# Crazebird-v0_5.net
KiCad netlist of a schematic drawn in EAGLE
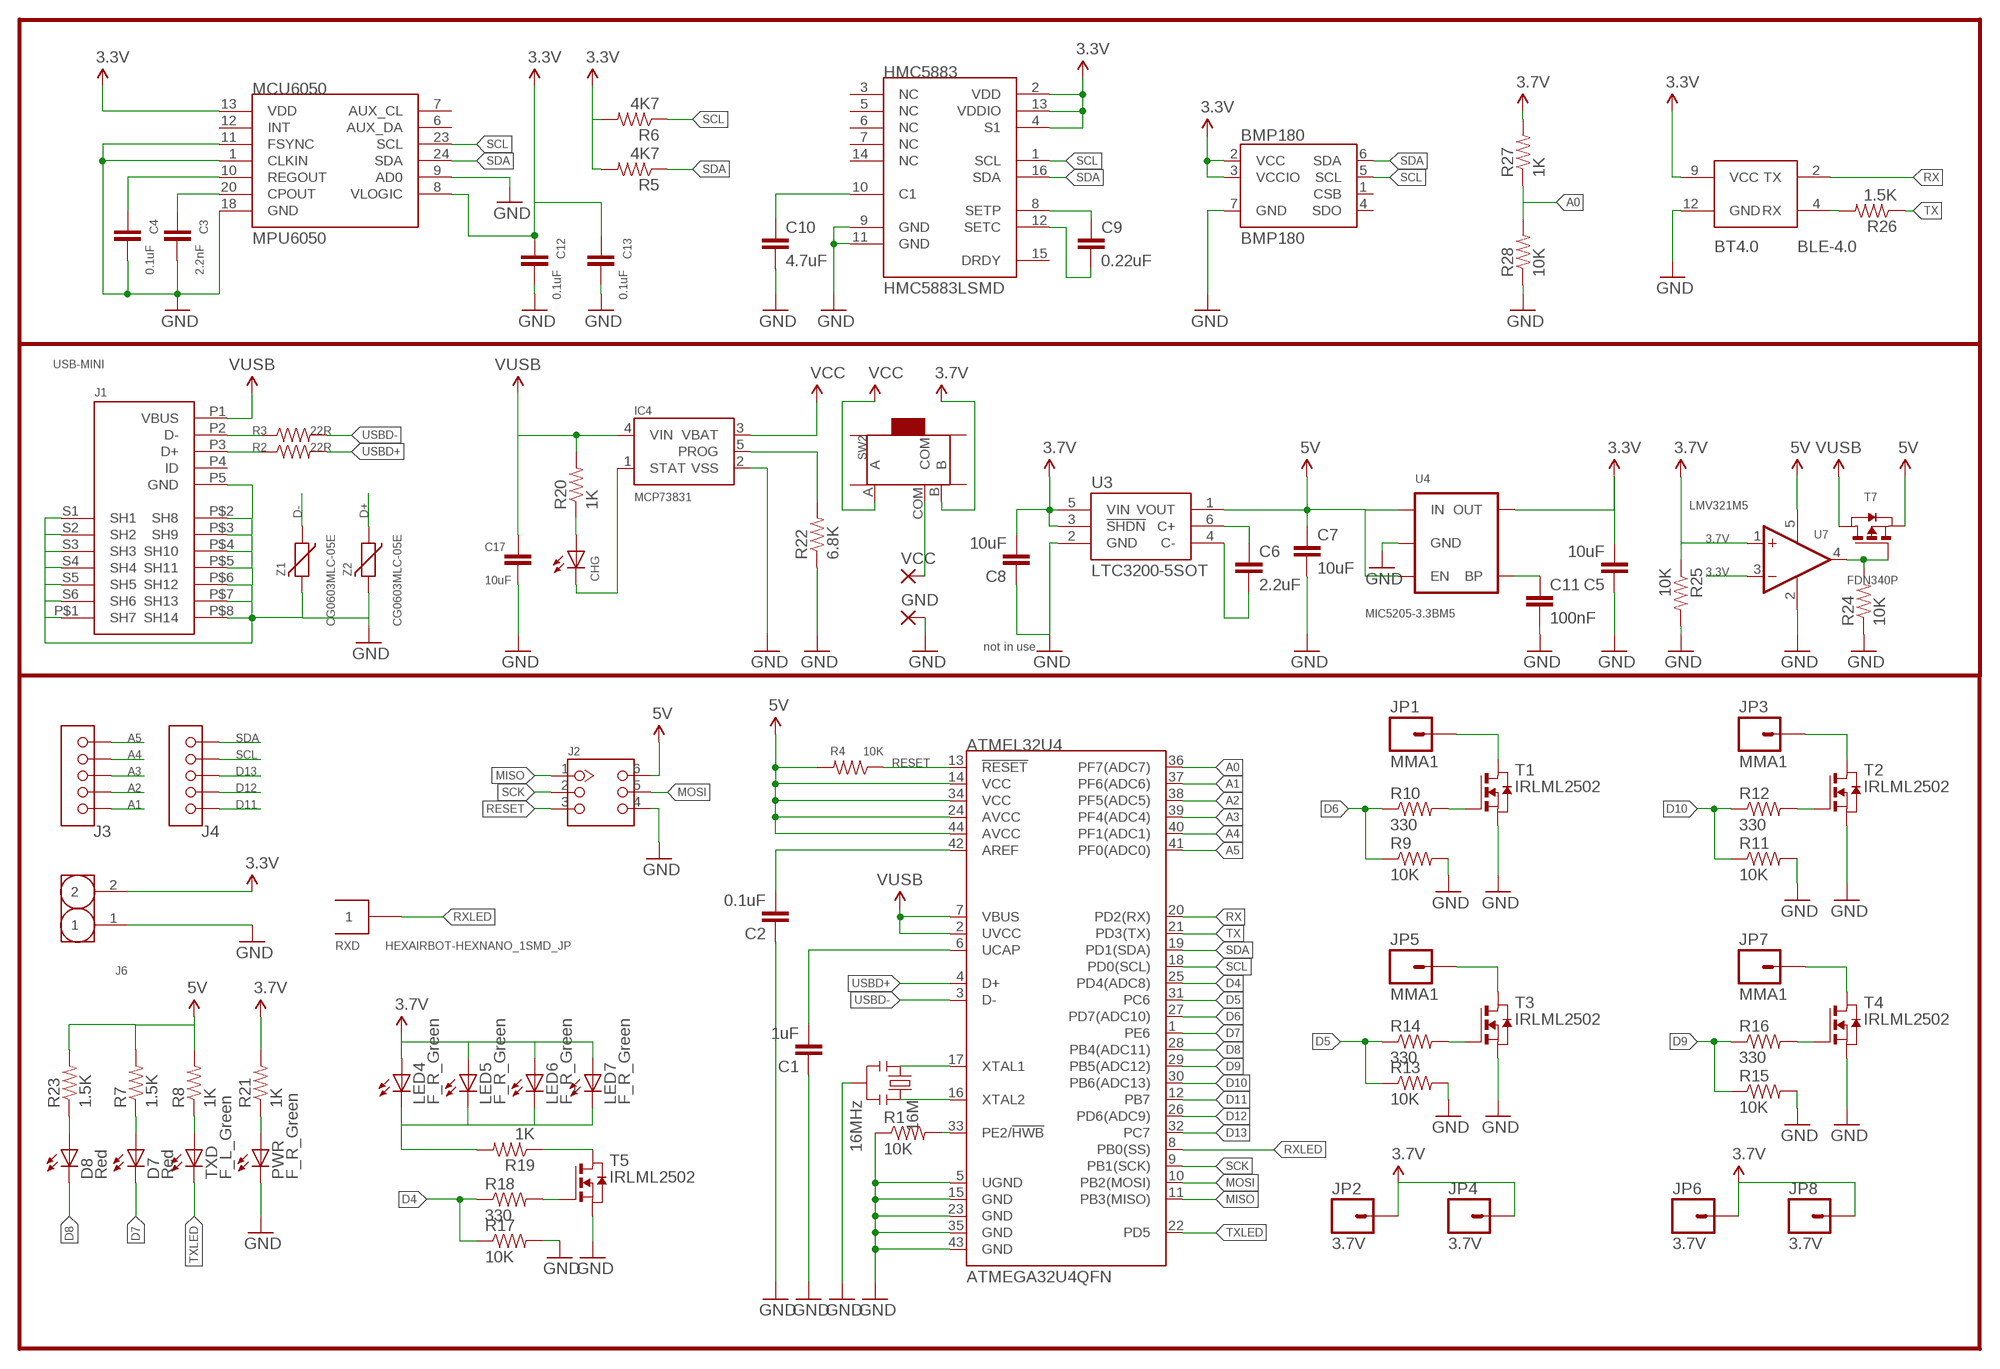
[diagram p0: schematic, sheet 1]

(export (version "E")
  (design (tool "Eeschema 10.0.6"))
  (components
    (comp (ref "16M")
      (value "16MHz")
      (footprint "eagle-import:RESONATOR-SMD")
      (libsource (lib "eagle-import") (part "RESONATOR16MHZ"))
    )
    (comp (ref "ATMEL32U4")
      (value "ATMEGA32U4QFN")
      (footprint "eagle-import:SPARKFUN-DIGITALIC_QFN-44")
      (libsource (lib "eagle-import") (part "ATMEGA32U4QFN"))
    )
    (comp (ref "BMP180")
      (value "BMP180")
      (footprint "eagle-import:BMP180")
      (libsource (lib "eagle-import") (part "BMP180"))
    )
    (comp (ref "BT4.0")
      (value "BLE-4.0")
      (footprint "eagle-import:HEXAIRBOT-HEXNANO_BLUETOOTH_HM11")
      (libsource (lib "eagle-import") (part "HEXAIRBOT-HEXNANO_BLUETOOTH_HM11"))
    )
    (comp (ref "C1")
      (value "1uF")
      (footprint "eagle-import:0402-CAP")
      (libsource (lib "eagle-import") (part "SparkFun-Passives_CAP0402-CAP"))
    )
    (comp (ref "C2")
      (value "0.1uF")
      (footprint "eagle-import:0402-CAP")
      (libsource (lib "eagle-import") (part "SparkFun-Passives_CAP0402-CAP"))
    )
    (comp (ref "C3")
      (value "2.2nF")
      (footprint "eagle-import:0402-CAP")
      (libsource (lib "eagle-import") (part "SparkFun-Passives_CAP0402-CAP"))
    )
    (comp (ref "C4")
      (value "0.1uF")
      (footprint "eagle-import:0402-CAP")
      (libsource (lib "eagle-import") (part "SparkFun-Passives_CAP0402-CAP"))
    )
    (comp (ref "C5")
      (value "10uF")
      (footprint "eagle-import:0402-CAP")
      (libsource (lib "eagle-import") (part "SparkFun-Passives_CAP0402-CAP"))
    )
    (comp (ref "C6")
      (value "2.2uF")
      (footprint "eagle-import:0603-CAP")
      (libsource (lib "eagle-import") (part "SparkFun-Passives_CAP0603-CAP"))
    )
    (comp (ref "C7")
      (value "10uF")
      (footprint "eagle-import:0603-CAP")
      (libsource (lib "eagle-import") (part "SparkFun-Passives_CAP0603-CAP"))
    )
    (comp (ref "C8")
      (value "10uF")
      (footprint "eagle-import:0805")
      (libsource (lib "eagle-import") (part "SparkFun-Passives_CAP0805"))
    )
    (comp (ref "C9")
      (value "0.22uF")
      (footprint "eagle-import:0402-CAP")
      (libsource (lib "eagle-import") (part "SparkFun-Passives_CAP0402-CAP"))
    )
    (comp (ref "C10")
      (value "4.7uF")
      (footprint "eagle-import:0402-CAP")
      (libsource (lib "eagle-import") (part "SparkFun-Passives_CAP0402-CAP"))
    )
    (comp (ref "C11")
      (value "100nF")
      (footprint "eagle-import:0603-CAP")
      (libsource (lib "eagle-import") (part "SparkFun-Passives_CAP0603-CAP"))
    )
    (comp (ref "C12")
      (value "0.1uF")
      (footprint "eagle-import:0402-CAP")
      (libsource (lib "eagle-import") (part "SparkFun-Passives_CAP0402-CAP"))
    )
    (comp (ref "C13")
      (value "0.1uF")
      (footprint "eagle-import:0402-CAP")
      (libsource (lib "eagle-import") (part "SparkFun-Passives_CAP0402-CAP"))
    )
    (comp (ref "C17")
      (value "10uF")
      (footprint "eagle-import:0805")
      (libsource (lib "eagle-import") (part "CAP0805"))
    )
    (comp (ref "CHG")
      (value "Yellow")
      (footprint "eagle-import:CHIPLED_0603")
      (libsource (lib "eagle-import") (part "LEDCHIPLED_0603"))
    )
    (comp (ref "D7")
      (value "Red")
      (footprint "eagle-import:CHIPLED_0603")
      (libsource (lib "eagle-import") (part "LEDCHIPLED_0603"))
    )
    (comp (ref "D8")
      (value "Red")
      (footprint "eagle-import:CHIPLED_0603")
      (libsource (lib "eagle-import") (part "LEDCHIPLED_0603"))
    )
    (comp (ref "GND")
      (value "2,15/1,0")
      (footprint "eagle-import:2,15_1,0")
      (libsource (lib "eagle-import") (part "2,15/1,0"))
    )
    (comp (ref "HMC5883")
      (value "HMC5883LSMD")
      (footprint "eagle-import:16LPCC")
      (libsource (lib "eagle-import") (part "HMC5883LSMD"))
    )
    (comp (ref "IC4")
      (value "MCP73831")
      (footprint "eagle-import:SOT23-5")
      (libsource (lib "eagle-import") (part "MCP73831"))
    )
    (comp (ref "J1")
      (value "USB-MINI")
      (footprint "eagle-import:USB_MICRO")
      (libsource (lib "eagle-import") (part "USB-MINI"))
    )
    (comp (ref "J2")
      (value "HEADER-2X3P-2.0")
      (footprint "eagle-import:2X3P-2.0")
      (libsource (lib "eagle-import") (part "HEADER-2X3P-2.0"))
    )
    (comp (ref "J3")
      (value "HEADER-5P-2.0")
      (footprint "eagle-import:5P-2.0")
      (libsource (lib "eagle-import") (part "HEADER-5P-2.0"))
    )
    (comp (ref "J4")
      (value "HEADER-5P-2.0")
      (footprint "eagle-import:5P-2.0")
      (libsource (lib "eagle-import") (part "HEADER-5P-2.0"))
    )
    (comp (ref "J6")
      (value "HEADER-2P-2.0")
      (footprint "eagle-import:2P-2.0")
      (libsource (lib "eagle-import") (part "HEADER-2P-2.0"))
    )
    (comp (ref "JP1")
      (value "MMA1")
      (footprint "eagle-import:PAD-1.5X4.5")
      (libsource (lib "eagle-import") (part "M01SMD-4.5X1.5"))
    )
    (comp (ref "JP2")
      (value "3.7V")
      (footprint "eagle-import:PAD-1.5X4.5")
      (libsource (lib "eagle-import") (part "M01SMD-4.5X1.5"))
    )
    (comp (ref "JP3")
      (value "MMA1")
      (footprint "eagle-import:PAD-1.5X4.5")
      (libsource (lib "eagle-import") (part "M01SMD-4.5X1.5"))
    )
    (comp (ref "JP4")
      (value "3.7V")
      (footprint "eagle-import:PAD-1.5X4.5")
      (libsource (lib "eagle-import") (part "M01SMD-4.5X1.5"))
    )
    (comp (ref "JP5")
      (value "MMA1")
      (footprint "eagle-import:PAD-1.5X4.5")
      (libsource (lib "eagle-import") (part "M01SMD-4.5X1.5"))
    )
    (comp (ref "JP6")
      (value "3.7V")
      (footprint "eagle-import:PAD-1.5X4.5")
      (libsource (lib "eagle-import") (part "M01SMD-4.5X1.5"))
    )
    (comp (ref "JP7")
      (value "MMA1")
      (footprint "eagle-import:PAD-1.5X4.5")
      (libsource (lib "eagle-import") (part "M01SMD-4.5X1.5"))
    )
    (comp (ref "JP8")
      (value "3.7V")
      (footprint "eagle-import:PAD-1.5X4.5")
      (libsource (lib "eagle-import") (part "M01SMD-4.5X1.5"))
    )
    (comp (ref "LED4")
      (value "F_R_Green")
      (footprint "eagle-import:CHIPLED_0603")
      (libsource (lib "eagle-import") (part "LEDCHIPLED_0603"))
    )
    (comp (ref "LED5")
      (value "F_R_Green")
      (footprint "eagle-import:CHIPLED_0603")
      (libsource (lib "eagle-import") (part "LEDCHIPLED_0603"))
    )
    (comp (ref "LED6")
      (value "F_R_Green")
      (footprint "eagle-import:CHIPLED_0603")
      (libsource (lib "eagle-import") (part "LEDCHIPLED_0603"))
    )
    (comp (ref "LED7")
      (value "F_R_Green")
      (footprint "eagle-import:CHIPLED_0603")
      (libsource (lib "eagle-import") (part "LEDCHIPLED_0603"))
    )
    (comp (ref "MCU6050")
      (value "MPU6050")
      (footprint "eagle-import:TESTING_QFN-24-4MM2")
      (libsource (lib "eagle-import") (part "TESTING_MPU-6050-1"))
    )
    (comp (ref "PWR")
      (value "F_R_Green")
      (footprint "eagle-import:CHIPLED_0603")
      (libsource (lib "eagle-import") (part "LEDCHIPLED_0603"))
    )
    (comp (ref "R1")
      (value "10K")
      (footprint "eagle-import:0402-RES")
      (libsource (lib "eagle-import") (part "RESISTOR0402-RES"))
    )
    (comp (ref "R2")
      (value "22R")
      (footprint "eagle-import:0402-RES")
      (libsource (lib "eagle-import") (part "RESISTOR0402-RES"))
    )
    (comp (ref "R3")
      (value "22R")
      (footprint "eagle-import:0402-RES")
      (libsource (lib "eagle-import") (part "RESISTOR0402-RES"))
    )
    (comp (ref "R4")
      (value "10K")
      (footprint "eagle-import:0402-RES")
      (libsource (lib "eagle-import") (part "RESISTOR0402-RES"))
    )
    (comp (ref "R5")
      (value "4K7")
      (footprint "eagle-import:0402-RES")
      (libsource (lib "eagle-import") (part "RESISTOR0402-RES"))
    )
    (comp (ref "R6")
      (value "4K7")
      (footprint "eagle-import:0402-RES")
      (libsource (lib "eagle-import") (part "RESISTOR0402-RES"))
    )
    (comp (ref "R7")
      (value "1.5K")
      (footprint "eagle-import:0402-RES")
      (libsource (lib "eagle-import") (part "RESISTOR0402-RES"))
    )
    (comp (ref "R8")
      (value "1K")
      (footprint "eagle-import:0402-RES")
      (libsource (lib "eagle-import") (part "RESISTOR0402-RES"))
    )
    (comp (ref "R9")
      (value "10K")
      (footprint "eagle-import:0402-RES")
      (libsource (lib "eagle-import") (part "RESISTOR0402-RES"))
    )
    (comp (ref "R10")
      (value "330")
      (footprint "eagle-import:0402-RES")
      (libsource (lib "eagle-import") (part "RESISTOR0402-RES"))
    )
    (comp (ref "R11")
      (value "10K")
      (footprint "eagle-import:0402-RES")
      (libsource (lib "eagle-import") (part "RESISTOR0402-RES"))
    )
    (comp (ref "R12")
      (value "330")
      (footprint "eagle-import:0402-RES")
      (libsource (lib "eagle-import") (part "RESISTOR0402-RES"))
    )
    (comp (ref "R13")
      (value "10K")
      (footprint "eagle-import:0402-RES")
      (libsource (lib "eagle-import") (part "RESISTOR0402-RES"))
    )
    (comp (ref "R14")
      (value "330")
      (footprint "eagle-import:0402-RES")
      (libsource (lib "eagle-import") (part "RESISTOR0402-RES"))
    )
    (comp (ref "R15")
      (value "10K")
      (footprint "eagle-import:0402-RES")
      (libsource (lib "eagle-import") (part "RESISTOR0402-RES"))
    )
    (comp (ref "R16")
      (value "330")
      (footprint "eagle-import:0402-RES")
      (libsource (lib "eagle-import") (part "RESISTOR0402-RES"))
    )
    (comp (ref "R17")
      (value "10K")
      (footprint "eagle-import:0402-RES")
      (libsource (lib "eagle-import") (part "RESISTOR0402-RES"))
    )
    (comp (ref "R18")
      (value "330")
      (footprint "eagle-import:0402-RES")
      (libsource (lib "eagle-import") (part "RESISTOR0402-RES"))
    )
    (comp (ref "R19")
      (value "1K")
      (footprint "eagle-import:0402-RES")
      (libsource (lib "eagle-import") (part "RESISTOR0402-RES"))
    )
    (comp (ref "R20")
      (value "1K")
      (footprint "eagle-import:0402-RES")
      (libsource (lib "eagle-import") (part "RESISTOR0402-RES"))
    )
    (comp (ref "R21")
      (value "1K")
      (footprint "eagle-import:0402-RES")
      (libsource (lib "eagle-import") (part "RESISTOR0402-RES"))
    )
    (comp (ref "R22")
      (value "6.8K")
      (footprint "eagle-import:0402-RES")
      (libsource (lib "eagle-import") (part "RESISTOR0402-RES"))
    )
    (comp (ref "R23")
      (value "1.5K")
      (footprint "eagle-import:0402-RES")
      (libsource (lib "eagle-import") (part "RESISTOR0402-RES"))
    )
    (comp (ref "R24")
      (value "10K")
      (footprint "eagle-import:0402-RES")
      (libsource (lib "eagle-import") (part "RESISTOR0402-RES"))
    )
    (comp (ref "R25")
      (value "10K")
      (footprint "eagle-import:0402-RES")
      (libsource (lib "eagle-import") (part "RESISTOR0402-RES"))
    )
    (comp (ref "R26")
      (value "1.5K")
      (footprint "eagle-import:0402-RES")
      (libsource (lib "eagle-import") (part "RESISTOR0402-RES"))
    )
    (comp (ref "R27")
      (value "1K")
      (footprint "eagle-import:0402-RES")
      (libsource (lib "eagle-import") (part "RESISTOR0402-RES"))
    )
    (comp (ref "R28")
      (value "10K")
      (footprint "eagle-import:0402-RES")
      (libsource (lib "eagle-import") (part "RESISTOR0402-RES"))
    )
    (comp (ref "RXD")
      (value "HEXAIRBOT-HEXNANO_1SMD_JP")
      (footprint "eagle-import:HEXAIRBOT-HEXNANO_1SMD")
      (libsource (lib "eagle-import") (part "HEXAIRBOT-HEXNANO_1SMD_JP"))
    )
    (comp (ref "SW2")
      (value "SWITCH-3P-SMD-6.6X2.8")
      (footprint "eagle-import:3P-SMD-2CH-6.6X2.8-REINFORCE")
      (libsource (lib "eagle-import") (part "SWITCH-3P-SMD-6.6X2.8"))
    )
    (comp (ref "T1")
      (value "IRLML2502")
      (footprint "eagle-import:SOT-23")
      (libsource (lib "eagle-import") (part "NMOSSOT23"))
    )
    (comp (ref "T2")
      (value "IRLML2502")
      (footprint "eagle-import:SOT-23")
      (libsource (lib "eagle-import") (part "NMOSSOT23"))
    )
    (comp (ref "T3")
      (value "IRLML2502")
      (footprint "eagle-import:SOT-23")
      (libsource (lib "eagle-import") (part "NMOSSOT23"))
    )
    (comp (ref "T4")
      (value "IRLML2502")
      (footprint "eagle-import:SOT-23")
      (libsource (lib "eagle-import") (part "NMOSSOT23"))
    )
    (comp (ref "T5")
      (value "IRLML2502")
      (footprint "eagle-import:SOT-23")
      (libsource (lib "eagle-import") (part "NMOSSOT23"))
    )
    (comp (ref "T7")
      (value "FDN340P")
      (footprint "eagle-import:SOT23")
      (libsource (lib "eagle-import") (part "FDN340P"))
    )
    (comp (ref "TXD")
      (value "F_L_Green")
      (footprint "eagle-import:CHIPLED_0603")
      (libsource (lib "eagle-import") (part "LEDCHIPLED_0603"))
    )
    (comp (ref "U3")
      (value "LTC3200-5SOT")
      (footprint "eagle-import:SOT23-6")
      (libsource (lib "eagle-import") (part "LTC3200-5SOT"))
    )
    (comp (ref "U4")
      (value "MIC5205-3.3BM5")
      (footprint "eagle-import:SOT23-5")
      (libsource (lib "eagle-import") (part "MIC52053.3V"))
    )
    (comp (ref "U7")
      (value "LMV321M5")
      (footprint "eagle-import:SOT23-5")
      (libsource (lib "eagle-import") (part "LMV321?M5"))
    )
    (comp (ref "VCC")
      (value "2,15/1,0")
      (footprint "eagle-import:2,15_1,0")
      (libsource (lib "eagle-import") (part "2,15/1,0"))
    )
    (comp (ref "Z1")
      (value "CG0603MLC-05E")
      (footprint "eagle-import:CT_CN0603")
      (libsource (lib "eagle-import") (part "VARISTORCN0603"))
    )
    (comp (ref "Z2")
      (value "CG0603MLC-05E")
      (footprint "eagle-import:CT_CN0603")
      (libsource (lib "eagle-import") (part "VARISTORCN0603"))
    )
  )
  (nets
    (net (code "1") (name "/D+") (class "Default")
      (node (ref "J1") (pin "P3") (pinfunction "D+_P3") (pintype "bidirectional"))
      (node (ref "R2") (pin "1") (pinfunction "1_1") (pintype "passive"))
      (node (ref "Z2") (pin "1") (pinfunction "1_1") (pintype "passive"))
    )
    (net (code "2") (name "/D-") (class "Default")
      (node (ref "J1") (pin "P2") (pinfunction "D-_P2") (pintype "bidirectional"))
      (node (ref "R3") (pin "1") (pinfunction "1_1") (pintype "passive"))
      (node (ref "Z1") (pin "1") (pinfunction "1_1") (pintype "passive"))
    )
    (net (code "3") (name "3.3V") (class "Default")
      (node (ref "BMP180") (pin "2") (pinfunction "VCC_2") (pintype "power_in"))
      (node (ref "BMP180") (pin "3") (pinfunction "VCCIO_3") (pintype "power_in"))
      (node (ref "BT4.0") (pin "9") (pinfunction "VCC_9") (pintype "bidirectional"))
      (node (ref "C12") (pin "1") (pinfunction "1_1") (pintype "passive"))
      (node (ref "C13") (pin "1") (pinfunction "1_1") (pintype "passive"))
      (node (ref "C5") (pin "2") (pinfunction "2_2") (pintype "passive"))
      (node (ref "HMC5883") (pin "13") (pinfunction "VDDIO_13") (pintype "bidirectional"))
      (node (ref "HMC5883") (pin "2") (pinfunction "VDD_2") (pintype "bidirectional"))
      (node (ref "HMC5883") (pin "4") (pinfunction "S1_4") (pintype "bidirectional"))
      (node (ref "J6") (pin "2") (pinfunction "2_2") (pintype "bidirectional"))
      (node (ref "MCU6050") (pin "13") (pinfunction "VDD_13") (pintype "bidirectional"))
      (node (ref "MCU6050") (pin "8") (pinfunction "VLOGIC_8") (pintype "bidirectional"))
      (node (ref "R5") (pin "2") (pinfunction "2_2") (pintype "passive"))
      (node (ref "R6") (pin "2") (pinfunction "2_2") (pintype "passive"))
      (node (ref "U4") (pin "5") (pinfunction "OUT_5") (pintype "passive"))
      (node (ref "U7") (pin "3") (pinfunction "-IN_3") (pintype "input"))
    )
    (net (code "4") (name "3.7V") (class "Default")
      (node (ref "C8") (pin "2") (pinfunction "2_2") (pintype "passive"))
      (node (ref "JP2") (pin "P$1") (pinfunction "1_P$1") (pintype "passive"))
      (node (ref "JP4") (pin "P$1") (pinfunction "1_P$1") (pintype "passive"))
      (node (ref "JP6") (pin "P$1") (pinfunction "1_P$1") (pintype "passive"))
      (node (ref "JP8") (pin "P$1") (pinfunction "1_P$1") (pintype "passive"))
      (node (ref "LED4") (pin "A") (pinfunction "A_A") (pintype "passive"))
      (node (ref "LED5") (pin "A") (pinfunction "A_A") (pintype "passive"))
      (node (ref "LED6") (pin "A") (pinfunction "A_A") (pintype "passive"))
      (node (ref "LED7") (pin "A") (pinfunction "A_A") (pintype "passive"))
      (node (ref "R21") (pin "2") (pinfunction "2_2") (pintype "passive"))
      (node (ref "R25") (pin "1") (pinfunction "1_1") (pintype "passive"))
      (node (ref "R27") (pin "2") (pinfunction "2_2") (pintype "passive"))
      (node (ref "SW2") (pin "B") (pinfunction "B_B") (pintype "bidirectional"))
      (node (ref "U3") (pin "3") (pinfunction "~{SHDN}_3") (pintype "bidirectional"))
      (node (ref "U3") (pin "5") (pinfunction "VIN_5") (pintype "bidirectional"))
      (node (ref "U7") (pin "1") (pinfunction "+IN_1") (pintype "input"))
    )
    (net (code "5") (name "5V") (class "Default")
      (node (ref "ATMEL32U4") (pin "14") (pinfunction "VCC_14") (pintype "bidirectional"))
      (node (ref "ATMEL32U4") (pin "24") (pinfunction "AVCC_24") (pintype "bidirectional"))
      (node (ref "ATMEL32U4") (pin "34") (pinfunction "VCC_34") (pintype "bidirectional"))
      (node (ref "ATMEL32U4") (pin "44") (pinfunction "AVCC_44") (pintype "bidirectional"))
      (node (ref "C7") (pin "1") (pinfunction "1_1") (pintype "passive"))
      (node (ref "J2") (pin "6") (pinfunction "6_6") (pintype "bidirectional"))
      (node (ref "R23") (pin "2") (pinfunction "2_2") (pintype "passive"))
      (node (ref "R4") (pin "2") (pinfunction "2_2") (pintype "passive"))
      (node (ref "R7") (pin "2") (pinfunction "2_2") (pintype "passive"))
      (node (ref "R8") (pin "2") (pinfunction "2_2") (pintype "passive"))
      (node (ref "T7") (pin "2") (pinfunction "S_2") (pintype "passive"))
      (node (ref "U3") (pin "1") (pinfunction "VOUT_1") (pintype "bidirectional"))
      (node (ref "U4") (pin "1") (pinfunction "IN_1") (pintype "input"))
      (node (ref "U4") (pin "3") (pinfunction "EN_3") (pintype "input"))
      (node (ref "U7") (pin "5") (pinfunction "V+_5") (pintype "power_in"))
    )
    (net (code "6") (name "A0") (class "Default")
      (node (ref "ATMEL32U4") (pin "36") (pinfunction "PF7(ADC7)_36") (pintype "bidirectional"))
      (node (ref "R27") (pin "1") (pinfunction "1_1") (pintype "passive"))
      (node (ref "R28") (pin "2") (pinfunction "2_2") (pintype "passive"))
    )
    (net (code "7") (name "A1") (class "Default")
      (node (ref "ATMEL32U4") (pin "37") (pinfunction "PF6(ADC6)_37") (pintype "bidirectional"))
      (node (ref "J3") (pin "1") (pinfunction "1_1") (pintype "bidirectional"))
    )
    (net (code "8") (name "A2") (class "Default")
      (node (ref "ATMEL32U4") (pin "38") (pinfunction "PF5(ADC5)_38") (pintype "bidirectional"))
      (node (ref "J3") (pin "2") (pinfunction "2_2") (pintype "bidirectional"))
    )
    (net (code "9") (name "A3") (class "Default")
      (node (ref "ATMEL32U4") (pin "39") (pinfunction "PF4(ADC4)_39") (pintype "bidirectional"))
      (node (ref "J3") (pin "3") (pinfunction "3_3") (pintype "bidirectional"))
    )
    (net (code "10") (name "A4") (class "Default")
      (node (ref "ATMEL32U4") (pin "40") (pinfunction "PF1(ADC1)_40") (pintype "bidirectional"))
      (node (ref "J3") (pin "4") (pinfunction "4_4") (pintype "bidirectional"))
    )
    (net (code "11") (name "A5") (class "Default")
      (node (ref "ATMEL32U4") (pin "41") (pinfunction "PF0(ADC0)_41") (pintype "bidirectional"))
      (node (ref "J3") (pin "5") (pinfunction "5_5") (pintype "bidirectional"))
    )
    (net (code "12") (name "D4") (class "Default")
      (node (ref "ATMEL32U4") (pin "25") (pinfunction "PD4(ADC8)_25") (pintype "bidirectional"))
      (node (ref "R17") (pin "1") (pinfunction "1_1") (pintype "passive"))
      (node (ref "R18") (pin "1") (pinfunction "1_1") (pintype "passive"))
    )
    (net (code "13") (name "D5") (class "Default")
      (node (ref "ATMEL32U4") (pin "31") (pinfunction "PC6_31") (pintype "bidirectional"))
      (node (ref "R13") (pin "1") (pinfunction "1_1") (pintype "passive"))
      (node (ref "R14") (pin "1") (pinfunction "1_1") (pintype "passive"))
    )
    (net (code "14") (name "D6") (class "Default")
      (node (ref "ATMEL32U4") (pin "27") (pinfunction "PD7(ADC10)_27") (pintype "bidirectional"))
      (node (ref "R10") (pin "1") (pinfunction "1_1") (pintype "passive"))
      (node (ref "R9") (pin "1") (pinfunction "1_1") (pintype "passive"))
    )
    (net (code "15") (name "D7") (class "Default")
      (node (ref "ATMEL32U4") (pin "1") (pinfunction "PE6_1") (pintype "bidirectional"))
      (node (ref "D7") (pin "C") (pinfunction "C_C") (pintype "passive"))
    )
    (net (code "16") (name "D8") (class "Default")
      (node (ref "ATMEL32U4") (pin "28") (pinfunction "PB4(ADC11)_28") (pintype "bidirectional"))
      (node (ref "D8") (pin "C") (pinfunction "C_C") (pintype "passive"))
    )
    (net (code "17") (name "D9") (class "Default")
      (node (ref "ATMEL32U4") (pin "29") (pinfunction "PB5(ADC12)_29") (pintype "bidirectional"))
      (node (ref "R15") (pin "1") (pinfunction "1_1") (pintype "passive"))
      (node (ref "R16") (pin "1") (pinfunction "1_1") (pintype "passive"))
    )
    (net (code "18") (name "D10") (class "Default")
      (node (ref "ATMEL32U4") (pin "30") (pinfunction "PB6(ADC13)_30") (pintype "bidirectional"))
      (node (ref "R11") (pin "1") (pinfunction "1_1") (pintype "passive"))
      (node (ref "R12") (pin "1") (pinfunction "1_1") (pintype "passive"))
    )
    (net (code "19") (name "D11") (class "Default")
      (node (ref "ATMEL32U4") (pin "12") (pinfunction "PB7_12") (pintype "bidirectional"))
      (node (ref "J4") (pin "1") (pinfunction "1_1") (pintype "bidirectional"))
    )
    (net (code "20") (name "D12") (class "Default")
      (node (ref "ATMEL32U4") (pin "26") (pinfunction "PD6(ADC9)_26") (pintype "bidirectional"))
      (node (ref "J4") (pin "2") (pinfunction "2_2") (pintype "bidirectional"))
    )
    (net (code "21") (name "D13") (class "Default")
      (node (ref "ATMEL32U4") (pin "32") (pinfunction "PC7_32") (pintype "bidirectional"))
      (node (ref "J4") (pin "3") (pinfunction "3_3") (pintype "bidirectional"))
    )
    (net (code "22") (name "GND") (class "Default")
      (node (ref "16M") (pin "2") (pinfunction "2_2") (pintype "passive"))
      (node (ref "ATMEL32U4") (pin "15") (pinfunction "GND_15") (pintype "bidirectional"))
      (node (ref "ATMEL32U4") (pin "23") (pinfunction "GND_23") (pintype "bidirectional"))
      (node (ref "ATMEL32U4") (pin "35") (pinfunction "GND_35") (pintype "bidirectional"))
      (node (ref "ATMEL32U4") (pin "43") (pinfunction "GND_43") (pintype "bidirectional"))
      (node (ref "ATMEL32U4") (pin "5") (pinfunction "UGND_5") (pintype "bidirectional"))
      (node (ref "BMP180") (pin "7") (pinfunction "GND_7") (pintype "power_in"))
      (node (ref "BT4.0") (pin "12") (pinfunction "GND_12") (pintype "bidirectional"))
      (node (ref "C1") (pin "1") (pinfunction "1_1") (pintype "passive"))
      (node (ref "C10") (pin "2") (pinfunction "2_2") (pintype "passive"))
      (node (ref "C11") (pin "2") (pinfunction "2_2") (pintype "passive"))
      (node (ref "C12") (pin "2") (pinfunction "2_2") (pintype "passive"))
      (node (ref "C13") (pin "2") (pinfunction "2_2") (pintype "passive"))
      (node (ref "C17") (pin "1") (pinfunction "1_1") (pintype "passive"))
      (node (ref "C2") (pin "1") (pinfunction "1_1") (pintype "passive"))
      (node (ref "C3") (pin "2") (pinfunction "2_2") (pintype "passive"))
      (node (ref "C4") (pin "2") (pinfunction "2_2") (pintype "passive"))
      (node (ref "C5") (pin "1") (pinfunction "1_1") (pintype "passive"))
      (node (ref "C7") (pin "2") (pinfunction "2_2") (pintype "passive"))
      (node (ref "C8") (pin "1") (pinfunction "1_1") (pintype "passive"))
      (node (ref "GND") (pin "1") (pinfunction "P_1") (pintype "passive"))
      (node (ref "HMC5883") (pin "11") (pinfunction "GND_11") (pintype "bidirectional"))
      (node (ref "HMC5883") (pin "9") (pinfunction "GND_9") (pintype "bidirectional"))
      (node (ref "IC4") (pin "2") (pinfunction "VSS_2") (pintype "power_in"))
      (node (ref "J1") (pin "P$1") (pinfunction "SH7_P$1") (pintype "passive"))
      (node (ref "J1") (pin "P$2") (pinfunction "SH8_P$2") (pintype "passive"))
      (node (ref "J1") (pin "P$3") (pinfunction "SH9_P$3") (pintype "passive"))
      (node (ref "J1") (pin "P$4") (pinfunction "SH10_P$4") (pintype "passive"))
      (node (ref "J1") (pin "P$5") (pinfunction "SH11_P$5") (pintype "passive"))
      (node (ref "J1") (pin "P$6") (pinfunction "SH12_P$6") (pintype "passive"))
      (node (ref "J1") (pin "P$7") (pinfunction "SH13_P$7") (pintype "passive"))
      (node (ref "J1") (pin "P$8") (pinfunction "SH14_P$8") (pintype "passive"))
      (node (ref "J1") (pin "P5") (pinfunction "GND_P5") (pintype "passive"))
      (node (ref "J1") (pin "S1") (pinfunction "SH1_S1") (pintype "passive"))
      (node (ref "J1") (pin "S2") (pinfunction "SH2_S2") (pintype "passive"))
      (node (ref "J1") (pin "S3") (pinfunction "SH3_S3") (pintype "passive"))
      (node (ref "J1") (pin "S4") (pinfunction "SH4_S4") (pintype "passive"))
      (node (ref "J1") (pin "S5") (pinfunction "SH5_S5") (pintype "passive"))
      (node (ref "J1") (pin "S6") (pinfunction "SH6_S6") (pintype "passive"))
      (node (ref "J2") (pin "4") (pinfunction "4_4") (pintype "bidirectional"))
      (node (ref "J6") (pin "1") (pinfunction "1_1") (pintype "bidirectional"))
      (node (ref "MCU6050") (pin "1") (pinfunction "CLKIN_1") (pintype "bidirectional"))
      (node (ref "MCU6050") (pin "11") (pinfunction "FSYNC_11") (pintype "bidirectional"))
      (node (ref "MCU6050") (pin "18") (pinfunction "GND_18") (pintype "bidirectional"))
      (node (ref "MCU6050") (pin "9") (pinfunction "AD0_9") (pintype "bidirectional"))
      (node (ref "PWR") (pin "C") (pinfunction "C_C") (pintype "passive"))
      (node (ref "R1") (pin "1") (pinfunction "1_1") (pintype "passive"))
      (node (ref "R11") (pin "2") (pinfunction "2_2") (pintype "passive"))
      (node (ref "R13") (pin "2") (pinfunction "2_2") (pintype "passive"))
      (node (ref "R15") (pin "2") (pinfunction "2_2") (pintype "passive"))
      (node (ref "R17") (pin "2") (pinfunction "2_2") (pintype "passive"))
      (node (ref "R22") (pin "1") (pinfunction "1_1") (pintype "passive"))
      (node (ref "R24") (pin "1") (pinfunction "1_1") (pintype "passive"))
      (node (ref "R25") (pin "2") (pinfunction "2_2") (pintype "passive"))
      (node (ref "R28") (pin "1") (pinfunction "1_1") (pintype "passive"))
      (node (ref "R9") (pin "2") (pinfunction "2_2") (pintype "passive"))
      (node (ref "T1") (pin "2") (pinfunction "S_2") (pintype "passive"))
      (node (ref "T2") (pin "2") (pinfunction "S_2") (pintype "passive"))
      (node (ref "T3") (pin "2") (pinfunction "S_2") (pintype "passive"))
      (node (ref "T4") (pin "2") (pinfunction "S_2") (pintype "passive"))
      (node (ref "T5") (pin "2") (pinfunction "S_2") (pintype "passive"))
      (node (ref "U3") (pin "2") (pinfunction "GND_2") (pintype "bidirectional"))
      (node (ref "U4") (pin "2") (pinfunction "GND_2") (pintype "input"))
      (node (ref "U7") (pin "2") (pinfunction "V-_2") (pintype "power_in"))
      (node (ref "Z1") (pin "2") (pinfunction "2_2") (pintype "passive"))
      (node (ref "Z2") (pin "2") (pinfunction "2_2") (pintype "passive"))
    )
    (net (code "23") (name "MISO") (class "Default")
      (node (ref "ATMEL32U4") (pin "11") (pinfunction "PB3(MISO)_11") (pintype "bidirectional"))
      (node (ref "J2") (pin "1") (pinfunction "1_1") (pintype "bidirectional"))
    )
    (net (code "24") (name "MOSI") (class "Default")
      (node (ref "ATMEL32U4") (pin "10") (pinfunction "PB2(MOSI)_10") (pintype "bidirectional"))
      (node (ref "J2") (pin "5") (pinfunction "5_5") (pintype "bidirectional"))
    )
    (net (code "25") (name "Net-(ATMEL32U4-AREF)") (class "Default")
      (node (ref "ATMEL32U4") (pin "42") (pinfunction "AREF_42") (pintype "bidirectional"))
      (node (ref "C2") (pin "2") (pinfunction "2_2") (pintype "passive"))
    )
    (net (code "26") (name "Net-(ATMEL32U4-PE2{slash}~{HWB})") (class "Default")
      (node (ref "ATMEL32U4") (pin "33") (pinfunction "PE2/~{HWB}_33") (pintype "bidirectional"))
      (node (ref "R1") (pin "2") (pinfunction "2_2") (pintype "passive"))
    )
    (net (code "27") (name "Net-(ATMEL32U4-UCAP)") (class "Default")
      (node (ref "ATMEL32U4") (pin "6") (pinfunction "UCAP_6") (pintype "bidirectional"))
      (node (ref "C1") (pin "2") (pinfunction "2_2") (pintype "passive"))
    )
    (net (code "28") (name "Net-(ATMEL32U4-XTAL1)") (class "Default")
      (node (ref "16M") (pin "1") (pinfunction "1_1") (pintype "passive"))
      (node (ref "ATMEL32U4") (pin "17") (pinfunction "XTAL1_17") (pintype "bidirectional"))
    )
    (net (code "29") (name "Net-(ATMEL32U4-XTAL2)") (class "Default")
      (node (ref "16M") (pin "3") (pinfunction "3_3") (pintype "passive"))
      (node (ref "ATMEL32U4") (pin "16") (pinfunction "XTAL2_16") (pintype "bidirectional"))
    )
    (net (code "30") (name "Net-(BT4.0-RX)") (class "Default")
      (node (ref "BT4.0") (pin "4") (pinfunction "RX_4") (pintype "bidirectional"))
      (node (ref "R26") (pin "2") (pinfunction "2_2") (pintype "passive"))
    )
    (net (code "31") (name "Net-(CHG-PadA)") (class "Default")
      (node (ref "CHG") (pin "A") (pinfunction "A_A") (pintype "passive"))
      (node (ref "R20") (pin "1") (pinfunction "1_1") (pintype "passive"))
    )
    (net (code "32") (name "Net-(D7-PadA)") (class "Default")
      (node (ref "D7") (pin "A") (pinfunction "A_A") (pintype "passive"))
      (node (ref "R7") (pin "1") (pinfunction "1_1") (pintype "passive"))
    )
    (net (code "33") (name "Net-(D8-PadA)") (class "Default")
      (node (ref "D8") (pin "A") (pinfunction "A_A") (pintype "passive"))
      (node (ref "R23") (pin "1") (pinfunction "1_1") (pintype "passive"))
    )
    (net (code "34") (name "Net-(HMC5883-C1)") (class "Default")
      (node (ref "C10") (pin "1") (pinfunction "1_1") (pintype "passive"))
      (node (ref "HMC5883") (pin "10") (pinfunction "C1_10") (pintype "bidirectional"))
    )
    (net (code "35") (name "Net-(HMC5883-SETC)") (class "Default")
      (node (ref "C9") (pin "2") (pinfunction "2_2") (pintype "passive"))
      (node (ref "HMC5883") (pin "12") (pinfunction "SETC_12") (pintype "bidirectional"))
    )
    (net (code "36") (name "Net-(HMC5883-SETP)") (class "Default")
      (node (ref "C9") (pin "1") (pinfunction "1_1") (pintype "passive"))
      (node (ref "HMC5883") (pin "8") (pinfunction "SETP_8") (pintype "bidirectional"))
    )
    (net (code "37") (name "Net-(IC4-PROG)") (class "Default")
      (node (ref "IC4") (pin "5") (pinfunction "PROG_5") (pintype "input"))
      (node (ref "R22") (pin "2") (pinfunction "2_2") (pintype "passive"))
    )
    (net (code "38") (name "Net-(IC4-STAT)") (class "Default")
      (node (ref "CHG") (pin "C") (pinfunction "C_C") (pintype "passive"))
      (node (ref "IC4") (pin "1") (pinfunction "STAT_1") (pintype "output"))
    )
    (net (code "39") (name "Net-(JP1-1)") (class "Default")
      (node (ref "JP1") (pin "P$1") (pinfunction "1_P$1") (pintype "passive"))
      (node (ref "T1") (pin "1") (pinfunction "D_1") (pintype "passive"))
    )
    (net (code "40") (name "Net-(JP3-1)") (class "Default")
      (node (ref "JP3") (pin "P$1") (pinfunction "1_P$1") (pintype "passive"))
      (node (ref "T2") (pin "1") (pinfunction "D_1") (pintype "passive"))
    )
    (net (code "41") (name "Net-(JP5-1)") (class "Default")
      (node (ref "JP5") (pin "P$1") (pinfunction "1_P$1") (pintype "passive"))
      (node (ref "T3") (pin "1") (pinfunction "D_1") (pintype "passive"))
    )
    (net (code "42") (name "Net-(JP7-1)") (class "Default")
      (node (ref "JP7") (pin "P$1") (pinfunction "1_P$1") (pintype "passive"))
      (node (ref "T4") (pin "1") (pinfunction "D_1") (pintype "passive"))
    )
    (net (code "43") (name "Net-(LED4-PadC)") (class "Default")
      (node (ref "LED4") (pin "C") (pinfunction "C_C") (pintype "passive"))
      (node (ref "LED5") (pin "C") (pinfunction "C_C") (pintype "passive"))
      (node (ref "LED6") (pin "C") (pinfunction "C_C") (pintype "passive"))
      (node (ref "LED7") (pin "C") (pinfunction "C_C") (pintype "passive"))
      (node (ref "R19") (pin "2") (pinfunction "2_2") (pintype "passive"))
    )
    (net (code "44") (name "Net-(MCU6050-CPOUT)") (class "Default")
      (node (ref "C3") (pin "1") (pinfunction "1_1") (pintype "passive"))
      (node (ref "MCU6050") (pin "20") (pinfunction "CPOUT_20") (pintype "bidirectional"))
    )
    (net (code "45") (name "Net-(MCU6050-REGOUT)") (class "Default")
      (node (ref "C4") (pin "1") (pinfunction "1_1") (pintype "passive"))
      (node (ref "MCU6050") (pin "10") (pinfunction "REGOUT_10") (pintype "bidirectional"))
    )
    (net (code "46") (name "Net-(PWR-PadA)") (class "Default")
      (node (ref "PWR") (pin "A") (pinfunction "A_A") (pintype "passive"))
      (node (ref "R21") (pin "1") (pinfunction "1_1") (pintype "passive"))
    )
    (net (code "47") (name "Net-(R8-Pad1)") (class "Default")
      (node (ref "R8") (pin "1") (pinfunction "1_1") (pintype "passive"))
      (node (ref "TXD") (pin "A") (pinfunction "A_A") (pintype "passive"))
    )
    (net (code "48") (name "Net-(T1-G)") (class "Default")
      (node (ref "R10") (pin "2") (pinfunction "2_2") (pintype "passive"))
      (node (ref "T1") (pin "3") (pinfunction "G_3") (pintype "passive"))
    )
    (net (code "49") (name "Net-(T2-G)") (class "Default")
      (node (ref "R12") (pin "2") (pinfunction "2_2") (pintype "passive"))
      (node (ref "T2") (pin "3") (pinfunction "G_3") (pintype "passive"))
    )
    (net (code "50") (name "Net-(T3-G)") (class "Default")
      (node (ref "R14") (pin "2") (pinfunction "2_2") (pintype "passive"))
      (node (ref "T3") (pin "3") (pinfunction "G_3") (pintype "passive"))
    )
    (net (code "51") (name "Net-(T4-G)") (class "Default")
      (node (ref "R16") (pin "2") (pinfunction "2_2") (pintype "passive"))
      (node (ref "T4") (pin "3") (pinfunction "G_3") (pintype "passive"))
    )
    (net (code "52") (name "Net-(T5-D)") (class "Default")
      (node (ref "R19") (pin "1") (pinfunction "1_1") (pintype "passive"))
      (node (ref "T5") (pin "1") (pinfunction "D_1") (pintype "passive"))
    )
    (net (code "53") (name "Net-(T5-G)") (class "Default")
      (node (ref "R18") (pin "2") (pinfunction "2_2") (pintype "passive"))
      (node (ref "T5") (pin "3") (pinfunction "G_3") (pintype "passive"))
    )
    (net (code "54") (name "Net-(T7-G)") (class "Default")
      (node (ref "R24") (pin "2") (pinfunction "2_2") (pintype "passive"))
      (node (ref "T7") (pin "3") (pinfunction "G_3") (pintype "passive"))
      (node (ref "U7") (pin "4") (pinfunction "OUT_4") (pintype "output"))
    )
    (net (code "55") (name "Net-(U3-C+)") (class "Default")
      (node (ref "C6") (pin "1") (pinfunction "1_1") (pintype "passive"))
      (node (ref "U3") (pin "6") (pinfunction "C+_6") (pintype "bidirectional"))
    )
    (net (code "56") (name "Net-(U3-C-)") (class "Default")
      (node (ref "C6") (pin "2") (pinfunction "2_2") (pintype "passive"))
      (node (ref "U3") (pin "4") (pinfunction "C-_4") (pintype "bidirectional"))
    )
    (net (code "57") (name "Net-(U4-BP)") (class "Default")
      (node (ref "C11") (pin "1") (pinfunction "1_1") (pintype "passive"))
      (node (ref "U4") (pin "4") (pinfunction "BP_4") (pintype "input"))
    )
    (net (code "58") (name "Net-(VCC-P)") (class "Default")
      (node (ref "SW2") (pin "COM") (pinfunction "COM_COM") (pintype "bidirectional"))
      (node (ref "VCC") (pin "1") (pinfunction "P_1") (pintype "passive"))
    )
    (net (code "59") (name "RESET") (class "Default")
      (node (ref "ATMEL32U4") (pin "13") (pinfunction "~{RESET}_13") (pintype "bidirectional"))
      (node (ref "J2") (pin "3") (pinfunction "3_3") (pintype "bidirectional"))
      (node (ref "R4") (pin "1") (pinfunction "1_1") (pintype "passive"))
    )
    (net (code "60") (name "RX") (class "Default")
      (node (ref "ATMEL32U4") (pin "20") (pinfunction "PD2(RX)_20") (pintype "bidirectional"))
      (node (ref "BT4.0") (pin "2") (pinfunction "TX_2") (pintype "bidirectional"))
    )
    (net (code "61") (name "RXLED") (class "Default")
      (node (ref "ATMEL32U4") (pin "8") (pinfunction "PB0(SS)_8") (pintype "bidirectional"))
      (node (ref "RXD") (pin "1") (pinfunction "1_1") (pintype "bidirectional"))
    )
    (net (code "62") (name "SCK") (class "Default")
      (node (ref "ATMEL32U4") (pin "9") (pinfunction "PB1(SCK)_9") (pintype "bidirectional"))
      (node (ref "J2") (pin "2") (pinfunction "2_2") (pintype "bidirectional"))
    )
    (net (code "63") (name "SCL") (class "Default")
      (node (ref "ATMEL32U4") (pin "18") (pinfunction "PD0(SCL)_18") (pintype "bidirectional"))
      (node (ref "BMP180") (pin "5") (pinfunction "SCL_5") (pintype "input"))
      (node (ref "HMC5883") (pin "1") (pinfunction "SCL_1") (pintype "bidirectional"))
      (node (ref "J4") (pin "4") (pinfunction "4_4") (pintype "bidirectional"))
      (node (ref "MCU6050") (pin "23") (pinfunction "SCL_23") (pintype "bidirectional"))
      (node (ref "R6") (pin "1") (pinfunction "1_1") (pintype "passive"))
    )
    (net (code "64") (name "SDA") (class "Default")
      (node (ref "ATMEL32U4") (pin "19") (pinfunction "PD1(SDA)_19") (pintype "bidirectional"))
      (node (ref "BMP180") (pin "6") (pinfunction "SDA_6") (pintype "bidirectional"))
      (node (ref "HMC5883") (pin "16") (pinfunction "SDA_16") (pintype "bidirectional"))
      (node (ref "J4") (pin "5") (pinfunction "5_5") (pintype "bidirectional"))
      (node (ref "MCU6050") (pin "24") (pinfunction "SDA_24") (pintype "bidirectional"))
      (node (ref "R5") (pin "1") (pinfunction "1_1") (pintype "passive"))
    )
    (net (code "65") (name "TX") (class "Default")
      (node (ref "ATMEL32U4") (pin "21") (pinfunction "PD3(TX)_21") (pintype "bidirectional"))
      (node (ref "R26") (pin "1") (pinfunction "1_1") (pintype "passive"))
    )
    (net (code "66") (name "TXLED") (class "Default")
      (node (ref "ATMEL32U4") (pin "22") (pinfunction "PD5_22") (pintype "bidirectional"))
      (node (ref "TXD") (pin "C") (pinfunction "C_C") (pintype "passive"))
    )
    (net (code "67") (name "USBD+") (class "Default")
      (node (ref "ATMEL32U4") (pin "4") (pinfunction "D+_4") (pintype "bidirectional"))
      (node (ref "R2") (pin "2") (pinfunction "2_2") (pintype "passive"))
    )
    (net (code "68") (name "USBD-") (class "Default")
      (node (ref "ATMEL32U4") (pin "3") (pinfunction "D-_3") (pintype "bidirectional"))
      (node (ref "R3") (pin "2") (pinfunction "2_2") (pintype "passive"))
    )
    (net (code "69") (name "VCC") (class "Default")
      (node (ref "IC4") (pin "3") (pinfunction "VBAT_3") (pintype "power_in"))
      (node (ref "SW2") (pin "A") (pinfunction "A_A") (pintype "bidirectional"))
    )
    (net (code "70") (name "VUSB") (class "Default")
      (node (ref "ATMEL32U4") (pin "2") (pinfunction "UVCC_2") (pintype "bidirectional"))
      (node (ref "ATMEL32U4") (pin "7") (pinfunction "VBUS_7") (pintype "bidirectional"))
      (node (ref "C17") (pin "2") (pinfunction "2_2") (pintype "passive"))
      (node (ref "IC4") (pin "4") (pinfunction "VIN_4") (pintype "power_in"))
      (node (ref "J1") (pin "P1") (pinfunction "VBUS_P1") (pintype "power_in"))
      (node (ref "R20") (pin "2") (pinfunction "2_2") (pintype "passive"))
      (node (ref "T7") (pin "1") (pinfunction "D_1") (pintype "passive"))
    )
    (net (code "71") (name "unconnected-(BMP180-CSB-Pad1)") (class "Default")
      (node (ref "BMP180") (pin "1") (pinfunction "CSB_1") (pintype "output"))
    )
    (net (code "72") (name "unconnected-(BMP180-SDO-Pad4)") (class "Default")
      (node (ref "BMP180") (pin "4") (pinfunction "SDO_4") (pintype "input"))
    )
    (net (code "73") (name "unconnected-(HMC5883-DRDY-Pad15)") (class "Default")
      (node (ref "HMC5883") (pin "15") (pinfunction "DRDY_15") (pintype "bidirectional"))
    )
    (net (code "74") (name "unconnected-(HMC5883-NC-Pad3)") (class "Default")
      (node (ref "HMC5883") (pin "3") (pinfunction "NC_3") (pintype "bidirectional"))
    )
    (net (code "75") (name "unconnected-(HMC5883-NC-Pad5)") (class "Default")
      (node (ref "HMC5883") (pin "5") (pinfunction "NC_5") (pintype "bidirectional"))
    )
    (net (code "76") (name "unconnected-(HMC5883-NC-Pad6)") (class "Default")
      (node (ref "HMC5883") (pin "6") (pinfunction "NC_6") (pintype "bidirectional"))
    )
    (net (code "77") (name "unconnected-(HMC5883-NC-Pad7)") (class "Default")
      (node (ref "HMC5883") (pin "7") (pinfunction "NC_7") (pintype "bidirectional"))
    )
    (net (code "78") (name "unconnected-(HMC5883-NC-Pad14)") (class "Default")
      (node (ref "HMC5883") (pin "14") (pinfunction "NC_14") (pintype "bidirectional"))
    )
    (net (code "79") (name "unconnected-(J1-ID-PadP4)") (class "Default")
      (node (ref "J1") (pin "P4") (pinfunction "ID_P4") (pintype "bidirectional"))
    )
    (net (code "80") (name "unconnected-(MCU6050-AUX_CL-Pad7)") (class "Default")
      (node (ref "MCU6050") (pin "7") (pinfunction "AUX_CL_7") (pintype "bidirectional"))
    )
    (net (code "81") (name "unconnected-(MCU6050-AUX_DA-Pad6)") (class "Default")
      (node (ref "MCU6050") (pin "6") (pinfunction "AUX_DA_6") (pintype "bidirectional"))
    )
    (net (code "82") (name "unconnected-(MCU6050-INT-Pad12)") (class "Default")
      (node (ref "MCU6050") (pin "12") (pinfunction "INT_12") (pintype "bidirectional"))
    )
    (net (code "83") (name "unconnected-(SW2-PadSS1)") (class "Default")
      (node (ref "SW2") (pin "SS1") (pinfunction "SS1_SS1") (pintype "bidirectional"))
    )
    (net (code "84") (name "unconnected-(SW2-PadSS2)") (class "Default")
      (node (ref "SW2") (pin "SS2") (pinfunction "SS2_SS2") (pintype "bidirectional"))
    )
    (net (code "85") (name "unconnected-(SW2-PadSS3)") (class "Default")
      (node (ref "SW2") (pin "SS3") (pinfunction "SS3_SS3") (pintype "bidirectional"))
    )
    (net (code "86") (name "unconnected-(SW2-PadSS4)") (class "Default")
      (node (ref "SW2") (pin "SS4") (pinfunction "SS4_SS4") (pintype "bidirectional"))
    )
  )
)
